# LPCB222_-_LINEAR_POT.net
KiCad netlist of a schematic drawn in Altium Designer
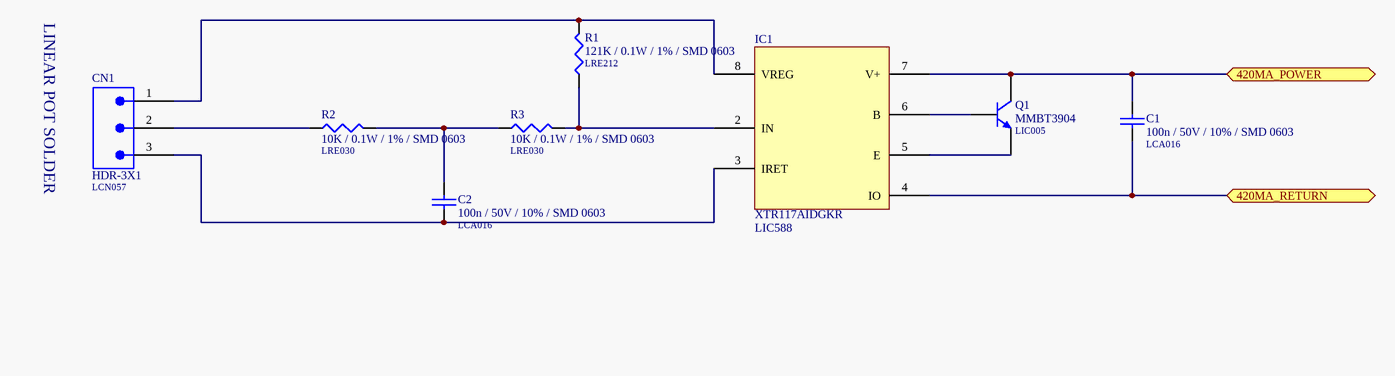
[diagram p0: LPCB222 - LINEAR POT.SchDoc]

(export (version "E")
  (design (tool "Eeschema 10.0.6"))
  (components
    (comp (ref "C1")
      (value "100n / 50V / 10% / SMD 0603")
      (footprint "LFP011__CC1608-0603-IPC7351_B")
      (description "Capacitor, Ceramic Chip, 100nF (0.1uF), 50V, 5%, SMD 0603 [LCA016]")
      (fields (field (name "LDL_NUMBER") "LCA016"))
      (libsource (lib "LDL_Capacitors") (part "100n / 50V / 10% / SMD 0603"))
    )
    (comp (ref "C2")
      (value "100n / 50V / 10% / SMD 0603")
      (footprint "LFP011__CC1608-0603-IPC7351_B")
      (description "Capacitor, Ceramic Chip, 100nF (0.1uF), 50V, 5%, SMD 0603 [LCA016]")
      (fields (field (name "LDL_NUMBER") "LCA016"))
      (libsource (lib "LDL_Capacitors") (part "100n / 50V / 10% / SMD 0603"))
    )
    (comp (ref "CN1")
      (value "HDR-3X1")
      (footprint "HDR-3X1")
      (description "Header, 2.54mm (0.1in), 3 Pins x 1 Row (40 Per Row In Strip)")
      (fields (field (name "LDL_NUMBER") "LCN057"))
      (libsource (lib "LDL_Connectors") (part "HDR-3X1"))
    )
    (comp (ref "IC1")
      (value "XTR117AIDGKR")
      (footprint "LFP015__UMAX8")
      (description "IC, 4-20mA Current Loop Transmitter, SMD SOIC8 [LIC588]")
      (fields (field (name "LDL_NUMBER") "LIC588"))
      (libsource (lib "LDL_Semiconductors") (part "XTR117AIDGKR"))
    )
    (comp (ref "Q1")
      (value "MMBT3904")
      (footprint "LFP021__SOT23")
      (description "Transistor, NPN, General Purpose, SOT-23 [LIC005]")
      (fields (field (name "LDL_NUMBER") "LIC005"))
      (libsource (lib "LDL_Semiconductors") (part "MMBT3904"))
    )
    (comp (ref "R1")
      (value "121K / 0.1W / 1% / SMD 0603")
      (footprint "LFP020__CR1608-0603-IPC7351_B")
      (description "Resistor, Ceramic Chip, 121K, 0.1W, SMD 0603 [LRE212]")
      (fields (field (name "LDL_NUMBER") "LRE212"))
      (libsource (lib "LDL_Resistors") (part "121K / 0.1W / 1% / SMD 0603"))
    )
    (comp (ref "R2")
      (value "10K / 0.1W / 1% / SMD 0603")
      (footprint "LFP020__CR1608-0603-IPC7351_B")
      (description "Resistor, Ceramic Chip, 10K, 0.1W, 1%, SMD 0603 [LRE030]")
      (fields (field (name "LDL_NUMBER") "LRE030"))
      (libsource (lib "LDL_Resistors") (part "10K / 0.1W / 1% / SMD 0603"))
    )
    (comp (ref "R3")
      (value "10K / 0.1W / 1% / SMD 0603")
      (footprint "LFP020__CR1608-0603-IPC7351_B")
      (description "Resistor, Ceramic Chip, 10K, 0.1W, 1%, SMD 0603 [LRE030]")
      (fields (field (name "LDL_NUMBER") "LRE030"))
      (libsource (lib "LDL_Resistors") (part "10K / 0.1W / 1% / SMD 0603"))
    )
  )
  (nets
    (net (code "1") (name "/420MA_POWER") (class "Default")
      (node (ref "C1") (pin "1") (pintype "passive"))
      (node (ref "IC1") (pin "7") (pinfunction "V+_7") (pintype "passive"))
      (node (ref "Q1") (pin "3") (pinfunction "C_3") (pintype "passive"))
    )
    (net (code "2") (name "/420MA_RETURN") (class "Default")
      (node (ref "C1") (pin "2") (pintype "passive"))
      (node (ref "IC1") (pin "4") (pinfunction "IO_4") (pintype "passive"))
    )
    (net (code "3") (name "Net-(C2-Pad1)") (class "Default")
      (node (ref "C2") (pin "1") (pintype "passive"))
      (node (ref "R2") (pin "2") (pintype "passive"))
      (node (ref "R3") (pin "1") (pintype "passive"))
    )
    (net (code "4") (name "Net-(CN1-Pad2)") (class "Default")
      (node (ref "CN1") (pin "2") (pinfunction "2_2") (pintype "passive"))
      (node (ref "R2") (pin "1") (pintype "passive"))
    )
    (net (code "5") (name "Net-(IC1-B)") (class "Default")
      (node (ref "IC1") (pin "6") (pinfunction "B_6") (pintype "passive"))
      (node (ref "Q1") (pin "1") (pinfunction "B_1") (pintype "passive"))
    )
    (net (code "6") (name "Net-(IC1-E)") (class "Default")
      (node (ref "IC1") (pin "5") (pinfunction "E_5") (pintype "passive"))
      (node (ref "Q1") (pin "2") (pinfunction "E_2") (pintype "passive"))
    )
    (net (code "7") (name "Net-(IC1-IN)") (class "Default")
      (node (ref "IC1") (pin "2") (pinfunction "IN_2") (pintype "passive"))
      (node (ref "R1") (pin "1") (pintype "passive"))
      (node (ref "R3") (pin "2") (pintype "passive"))
    )
    (net (code "8") (name "Net-(IC1-IRET)") (class "Default")
      (node (ref "C2") (pin "2") (pintype "passive"))
      (node (ref "CN1") (pin "3") (pinfunction "3_3") (pintype "passive"))
      (node (ref "IC1") (pin "3") (pinfunction "IRET_3") (pintype "passive"))
    )
    (net (code "9") (name "Net-(IC1-VREG)") (class "Default")
      (node (ref "CN1") (pin "1") (pinfunction "1_1") (pintype "passive"))
      (node (ref "IC1") (pin "8") (pinfunction "VREG_8") (pintype "passive"))
      (node (ref "R1") (pin "2") (pintype "passive"))
    )
  )
)
